# Rx.net
KiCad netlist of a schematic drawn in EAGLE
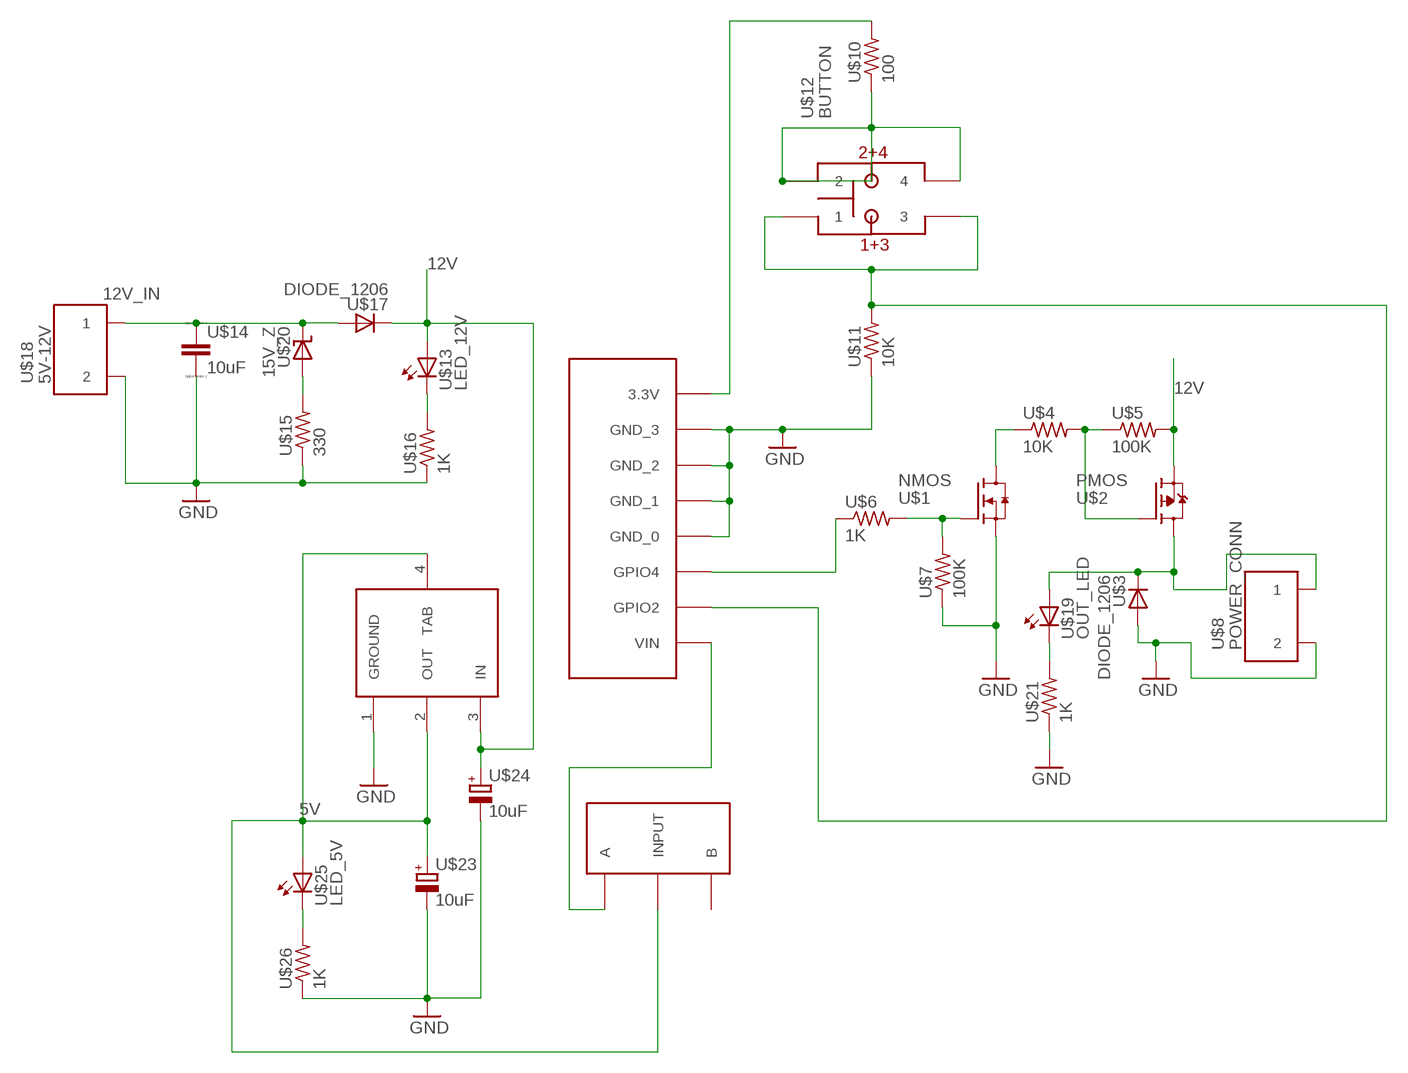
[diagram p0: schematic, sheet 1]

(export (version "E")
  (design (tool "Eeschema 10.0.6"))
  (components
    (comp (ref "U$1")
      (value "NMOS")
      (footprint "eagle-import:SOT23")
      (libsource (lib "eagle-import") (part "NMOS"))
    )
    (comp (ref "U$2")
      (value "PMOS")
      (footprint "eagle-import:D-PAK_TO252AA")
      (libsource (lib "eagle-import") (part "PMOS"))
    )
    (comp (ref "U$3")
      (value "DIODE_1206")
      (footprint "eagle-import:DIDOE_1206")
      (libsource (lib "eagle-import") (part "DIODE_1206"))
    )
    (comp (ref "U$4")
      (value "10K")
      (footprint "eagle-import:R1206")
      (libsource (lib "eagle-import") (part "RES"))
    )
    (comp (ref "U$5")
      (value "100K")
      (footprint "eagle-import:R1206")
      (libsource (lib "eagle-import") (part "RES"))
    )
    (comp (ref "U$6")
      (value "1K")
      (footprint "eagle-import:R1206")
      (libsource (lib "eagle-import") (part "RES"))
    )
    (comp (ref "U$7")
      (value "100K")
      (footprint "eagle-import:R1206")
      (libsource (lib "eagle-import") (part "RES"))
    )
    (comp (ref "U$8")
      (value "POWER_CONN")
      (footprint "eagle-import:PC_1935161")
      (libsource (lib "eagle-import") (part "POWER_CONN"))
    )
    (comp (ref "U$9")
      (value "ESP8266")
      (footprint "eagle-import:ESP")
      (libsource (lib "eagle-import") (part "ESP8266"))
    )
    (comp (ref "U$10")
      (value "100")
      (footprint "eagle-import:R1206")
      (libsource (lib "eagle-import") (part "RES"))
    )
    (comp (ref "U$11")
      (value "10K")
      (footprint "eagle-import:R1206")
      (libsource (lib "eagle-import") (part "RES"))
    )
    (comp (ref "U$12")
      (value "BUTTON")
      (footprint "eagle-import:BUTTON")
      (libsource (lib "eagle-import") (part "BUTTON"))
    )
    (comp (ref "U$13")
      (value "LED_12V")
      (footprint "eagle-import:LED_1206")
      (libsource (lib "eagle-import") (part "LED_1206"))
    )
    (comp (ref "U$14")
      (value "10uF")
      (footprint "eagle-import:C1206")
      (libsource (lib "eagle-import") (part "CAP"))
    )
    (comp (ref "U$15")
      (value "330")
      (footprint "eagle-import:R1206")
      (libsource (lib "eagle-import") (part "RES"))
    )
    (comp (ref "U$16")
      (value "1K")
      (footprint "eagle-import:R1206")
      (libsource (lib "eagle-import") (part "RES"))
    )
    (comp (ref "U$17")
      (value "DIODE_1206")
      (footprint "eagle-import:DIDOE_1206")
      (libsource (lib "eagle-import") (part "DIODE_1206"))
    )
    (comp (ref "U$18")
      (value "5V-12V")
      (footprint "eagle-import:PC_1935161")
      (libsource (lib "eagle-import") (part "POWER_CONN"))
    )
    (comp (ref "U$19")
      (value "OUT_LED")
      (footprint "eagle-import:LED_1206")
      (libsource (lib "eagle-import") (part "LED_1206"))
    )
    (comp (ref "U$20")
      (value "15V_Z")
      (footprint "eagle-import:Z_1005")
      (libsource (lib "eagle-import") (part "DIODE_Z_1005"))
    )
    (comp (ref "U$21")
      (value "1K")
      (footprint "eagle-import:R1206")
      (libsource (lib "eagle-import") (part "RES"))
    )
    (comp (ref "U$22")
      (value "5V_REG")
      (footprint "eagle-import:SOT223")
      (libsource (lib "eagle-import") (part "5V_REG"))
    )
    (comp (ref "U$23")
      (value "10uF")
      (footprint "eagle-import:153CLV-0405")
      (libsource (lib "eagle-import") (part "CAP_POL"))
    )
    (comp (ref "U$24")
      (value "10uF")
      (footprint "eagle-import:153CLV-0405")
      (libsource (lib "eagle-import") (part "CAP_POL"))
    )
    (comp (ref "U$25")
      (value "LED_5V")
      (footprint "eagle-import:LED_1206")
      (libsource (lib "eagle-import") (part "LED_1206"))
    )
    (comp (ref "U$26")
      (value "1K")
      (footprint "eagle-import:R1206")
      (libsource (lib "eagle-import") (part "RES"))
    )
    (comp (ref "U$27")
      (value "SPDT")
      (footprint "eagle-import:SPDT")
      (libsource (lib "eagle-import") (part "SPDT"))
    )
  )
  (nets
    (net (code "1") (name "/5V") (class "Default")
      (node (ref "U$22") (pin "2") (pinfunction "OUT_2") (pintype "bidirectional"))
      (node (ref "U$22") (pin "4") (pinfunction "TAB_4") (pintype "bidirectional"))
      (node (ref "U$23") (pin "+") (pinfunction "+_+") (pintype "passive"))
      (node (ref "U$25") (pin "1") (pinfunction "HI_1") (pintype "bidirectional"))
      (node (ref "U$27") (pin "IN") (pinfunction "INPUT_IN") (pintype "bidirectional"))
    )
    (net (code "2") (name "/12V") (class "Default")
      (node (ref "U$13") (pin "1") (pinfunction "HI_1") (pintype "bidirectional"))
      (node (ref "U$17") (pin "2") (pinfunction "LO_2") (pintype "bidirectional"))
      (node (ref "U$2") (pin "3") (pinfunction "S_3") (pintype "passive"))
      (node (ref "U$22") (pin "3") (pinfunction "IN_3") (pintype "bidirectional"))
      (node (ref "U$24") (pin "+") (pinfunction "+_+") (pintype "passive"))
      (node (ref "U$5") (pin "2") (pinfunction "2_2") (pintype "passive"))
    )
    (net (code "3") (name "/12V_IN") (class "Default")
      (node (ref "U$14") (pin "1") (pinfunction "1_1") (pintype "passive"))
      (node (ref "U$17") (pin "1") (pinfunction "HI_1") (pintype "bidirectional"))
      (node (ref "U$18") (pin "1") (pinfunction "1_1") (pintype "passive"))
      (node (ref "U$20") (pin "2") (pinfunction "LO_2") (pintype "bidirectional"))
    )
    (net (code "4") (name "GND") (class "Default")
      (node (ref "U$1") (pin "2") (pinfunction "S_2") (pintype "passive"))
      (node (ref "U$11") (pin "1") (pinfunction "1_1") (pintype "passive"))
      (node (ref "U$14") (pin "2") (pinfunction "2_2") (pintype "passive"))
      (node (ref "U$15") (pin "1") (pinfunction "1_1") (pintype "passive"))
      (node (ref "U$16") (pin "1") (pinfunction "1_1") (pintype "passive"))
      (node (ref "U$18") (pin "2") (pinfunction "2_2") (pintype "passive"))
      (node (ref "U$21") (pin "1") (pinfunction "1_1") (pintype "passive"))
      (node (ref "U$22") (pin "1") (pinfunction "GROUND_1") (pintype "bidirectional"))
      (node (ref "U$23") (pin "-") (pinfunction "-_-") (pintype "passive"))
      (node (ref "U$24") (pin "-") (pinfunction "-_-") (pintype "passive"))
      (node (ref "U$26") (pin "1") (pinfunction "1_1") (pintype "passive"))
      (node (ref "U$3") (pin "1") (pinfunction "HI_1") (pintype "bidirectional"))
      (node (ref "U$7") (pin "1") (pinfunction "1_1") (pintype "passive"))
      (node (ref "U$8") (pin "2") (pinfunction "2_2") (pintype "passive"))
      (node (ref "U$9") (pin "GND_0") (pinfunction "GND_0_GND_0") (pintype "bidirectional"))
      (node (ref "U$9") (pin "GND_1") (pinfunction "GND_1_GND_1") (pintype "bidirectional"))
      (node (ref "U$9") (pin "GND_2") (pinfunction "GND_2_GND_2") (pintype "bidirectional"))
      (node (ref "U$9") (pin "GND_3") (pinfunction "GND_3_GND_3") (pintype "bidirectional"))
    )
    (net (code "5") (name "Net-(U$1-D)") (class "Default")
      (node (ref "U$1") (pin "3") (pinfunction "D_3") (pintype "passive"))
      (node (ref "U$4") (pin "1") (pinfunction "1_1") (pintype "passive"))
    )
    (net (code "6") (name "Net-(U$1-G)") (class "Default")
      (node (ref "U$1") (pin "1") (pinfunction "G_1") (pintype "passive"))
      (node (ref "U$6") (pin "2") (pinfunction "2_2") (pintype "passive"))
      (node (ref "U$7") (pin "2") (pinfunction "2_2") (pintype "passive"))
    )
    (net (code "7") (name "Net-(U$2-G)") (class "Default")
      (node (ref "U$2") (pin "1") (pinfunction "G_1") (pintype "passive"))
      (node (ref "U$4") (pin "2") (pinfunction "2_2") (pintype "passive"))
      (node (ref "U$5") (pin "1") (pinfunction "1_1") (pintype "passive"))
    )
    (net (code "8") (name "Net-(U$6-Pad1)") (class "Default")
      (node (ref "U$6") (pin "1") (pinfunction "1_1") (pintype "passive"))
      (node (ref "U$9") (pin "GPIO4") (pinfunction "GPIO4_GPIO4") (pintype "bidirectional"))
    )
    (net (code "9") (name "Net-(U$9-3.3V)") (class "Default")
      (node (ref "U$10") (pin "2") (pinfunction "2_2") (pintype "passive"))
      (node (ref "U$9") (pin "3.3_1") (pinfunction "3.3V_3.3_1") (pintype "bidirectional"))
    )
    (net (code "10") (name "Net-(U$10-Pad1)") (class "Default")
      (node (ref "U$10") (pin "1") (pinfunction "1_1") (pintype "passive"))
      (node (ref "U$12") (pin "2") (pinfunction "2_2") (pintype "bidirectional"))
      (node (ref "U$12") (pin "4") (pinfunction "4_4") (pintype "bidirectional"))
    )
    (net (code "11") (name "Net-(U$11-Pad2)") (class "Default")
      (node (ref "U$11") (pin "2") (pinfunction "2_2") (pintype "passive"))
      (node (ref "U$12") (pin "1") (pinfunction "1_1") (pintype "bidirectional"))
      (node (ref "U$12") (pin "3") (pinfunction "3_3") (pintype "bidirectional"))
      (node (ref "U$9") (pin "GPIO2") (pinfunction "GPIO2_GPIO2") (pintype "bidirectional"))
    )
    (net (code "12") (name "Net-(U$13-LO)") (class "Default")
      (node (ref "U$13") (pin "2") (pinfunction "LO_2") (pintype "bidirectional"))
      (node (ref "U$16") (pin "2") (pinfunction "2_2") (pintype "passive"))
    )
    (net (code "13") (name "Net-(U$19-HI)") (class "Default")
      (node (ref "U$19") (pin "1") (pinfunction "HI_1") (pintype "bidirectional"))
      (node (ref "U$2") (pin "4") (pinfunction "D_4") (pintype "passive"))
      (node (ref "U$3") (pin "2") (pinfunction "LO_2") (pintype "bidirectional"))
      (node (ref "U$8") (pin "1") (pinfunction "1_1") (pintype "passive"))
    )
    (net (code "14") (name "Net-(U$19-LO)") (class "Default")
      (node (ref "U$19") (pin "2") (pinfunction "LO_2") (pintype "bidirectional"))
      (node (ref "U$21") (pin "2") (pinfunction "2_2") (pintype "passive"))
    )
    (net (code "15") (name "Net-(U$20-HI)") (class "Default")
      (node (ref "U$15") (pin "2") (pinfunction "2_2") (pintype "passive"))
      (node (ref "U$20") (pin "1") (pinfunction "HI_1") (pintype "bidirectional"))
    )
    (net (code "16") (name "Net-(U$25-LO)") (class "Default")
      (node (ref "U$25") (pin "2") (pinfunction "LO_2") (pintype "bidirectional"))
      (node (ref "U$26") (pin "2") (pinfunction "2_2") (pintype "passive"))
    )
    (net (code "17") (name "Net-(U$27-PadA)") (class "Default")
      (node (ref "U$27") (pin "A") (pinfunction "A_A") (pintype "bidirectional"))
      (node (ref "U$9") (pin "VIN") (pinfunction "VIN_VIN") (pintype "bidirectional"))
    )
    (net (code "18") (name "unconnected-(U$27-PadB)") (class "Default")
      (node (ref "U$27") (pin "B") (pinfunction "B_B") (pintype "bidirectional"))
    )
  )
)
